# MainBoard.net
KiCad netlist of a schematic drawn in EAGLE
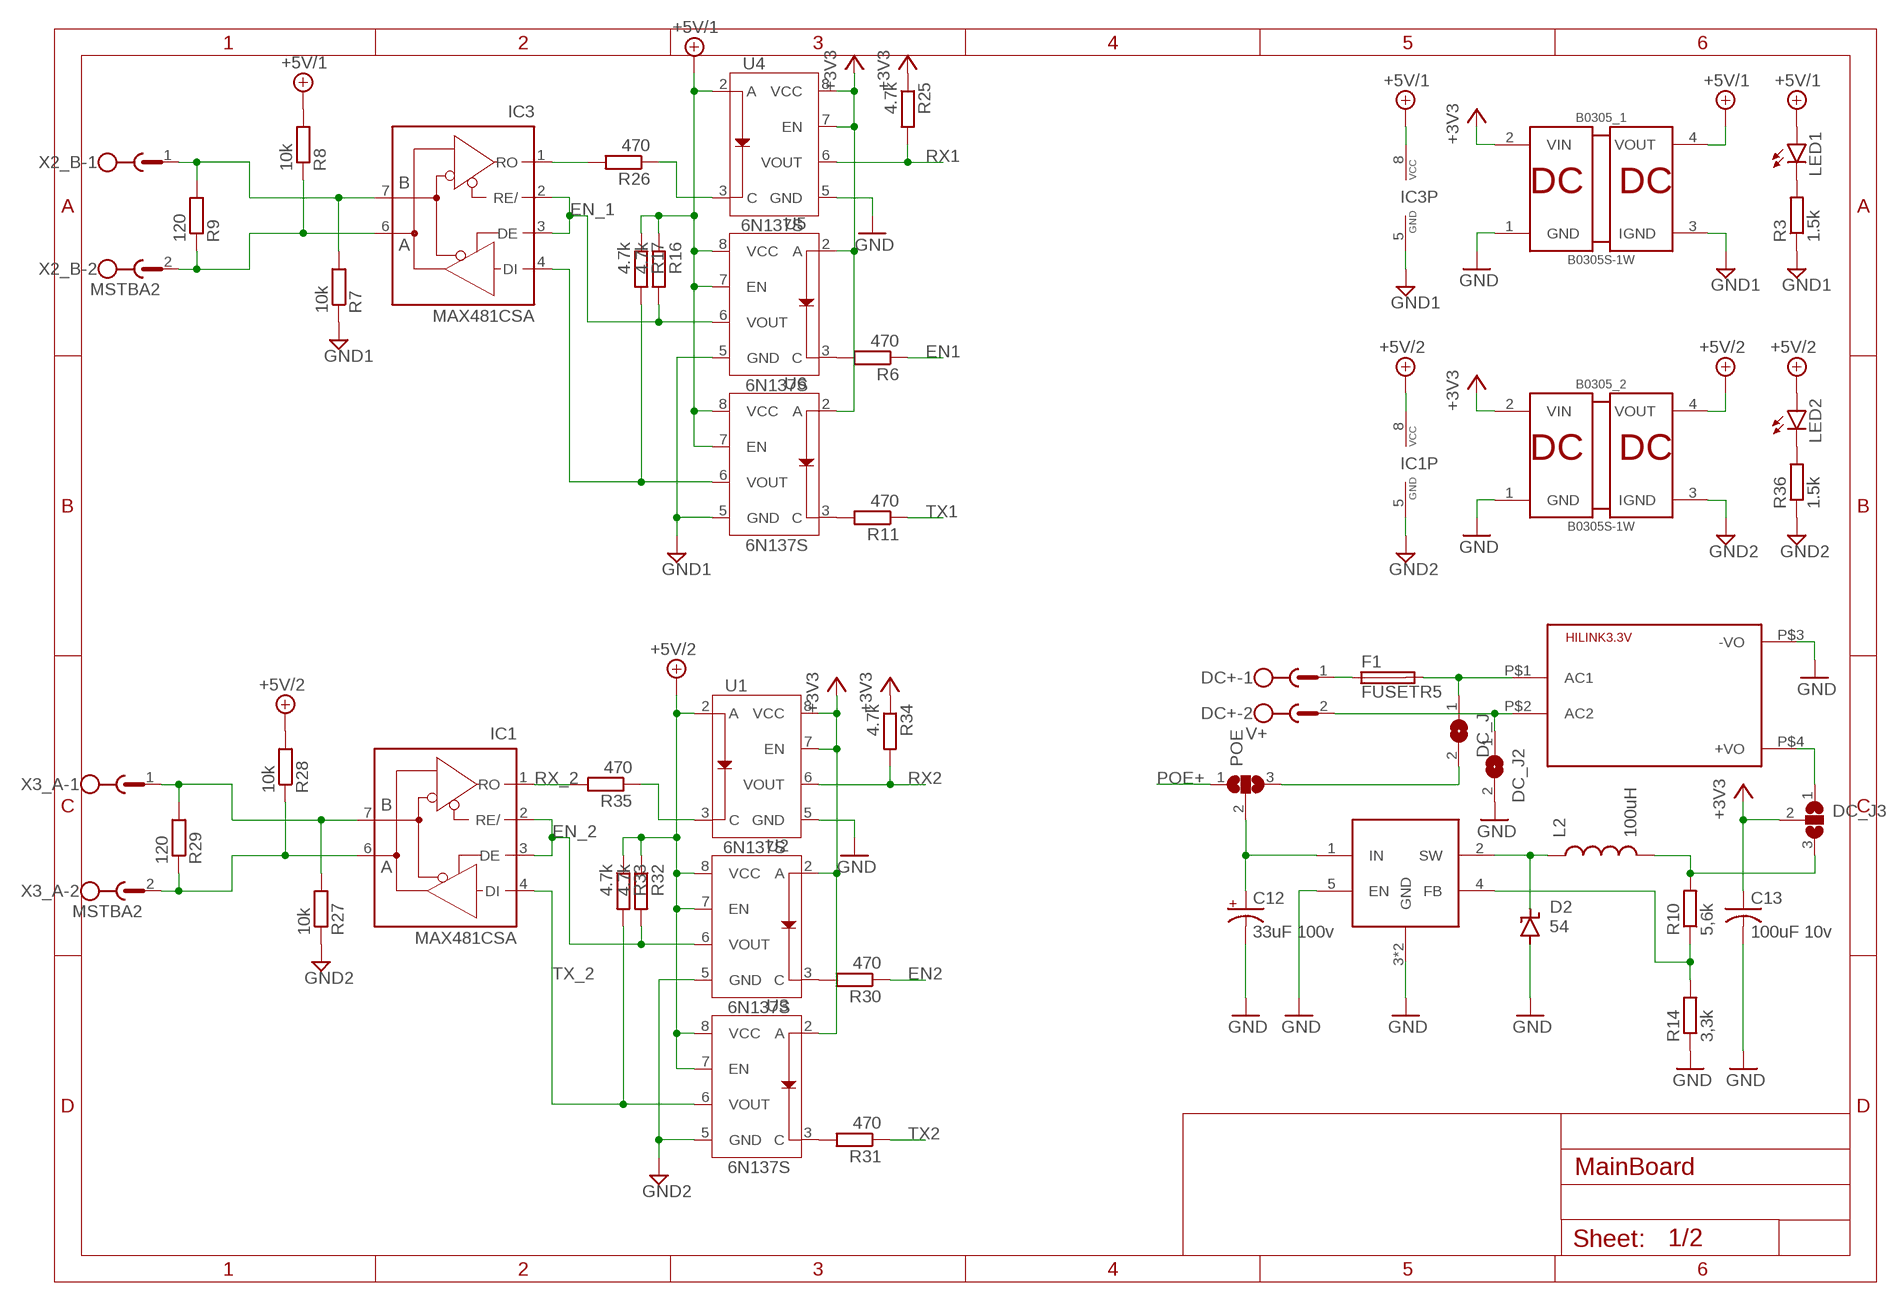
[diagram p0: schematic, sheet 1]
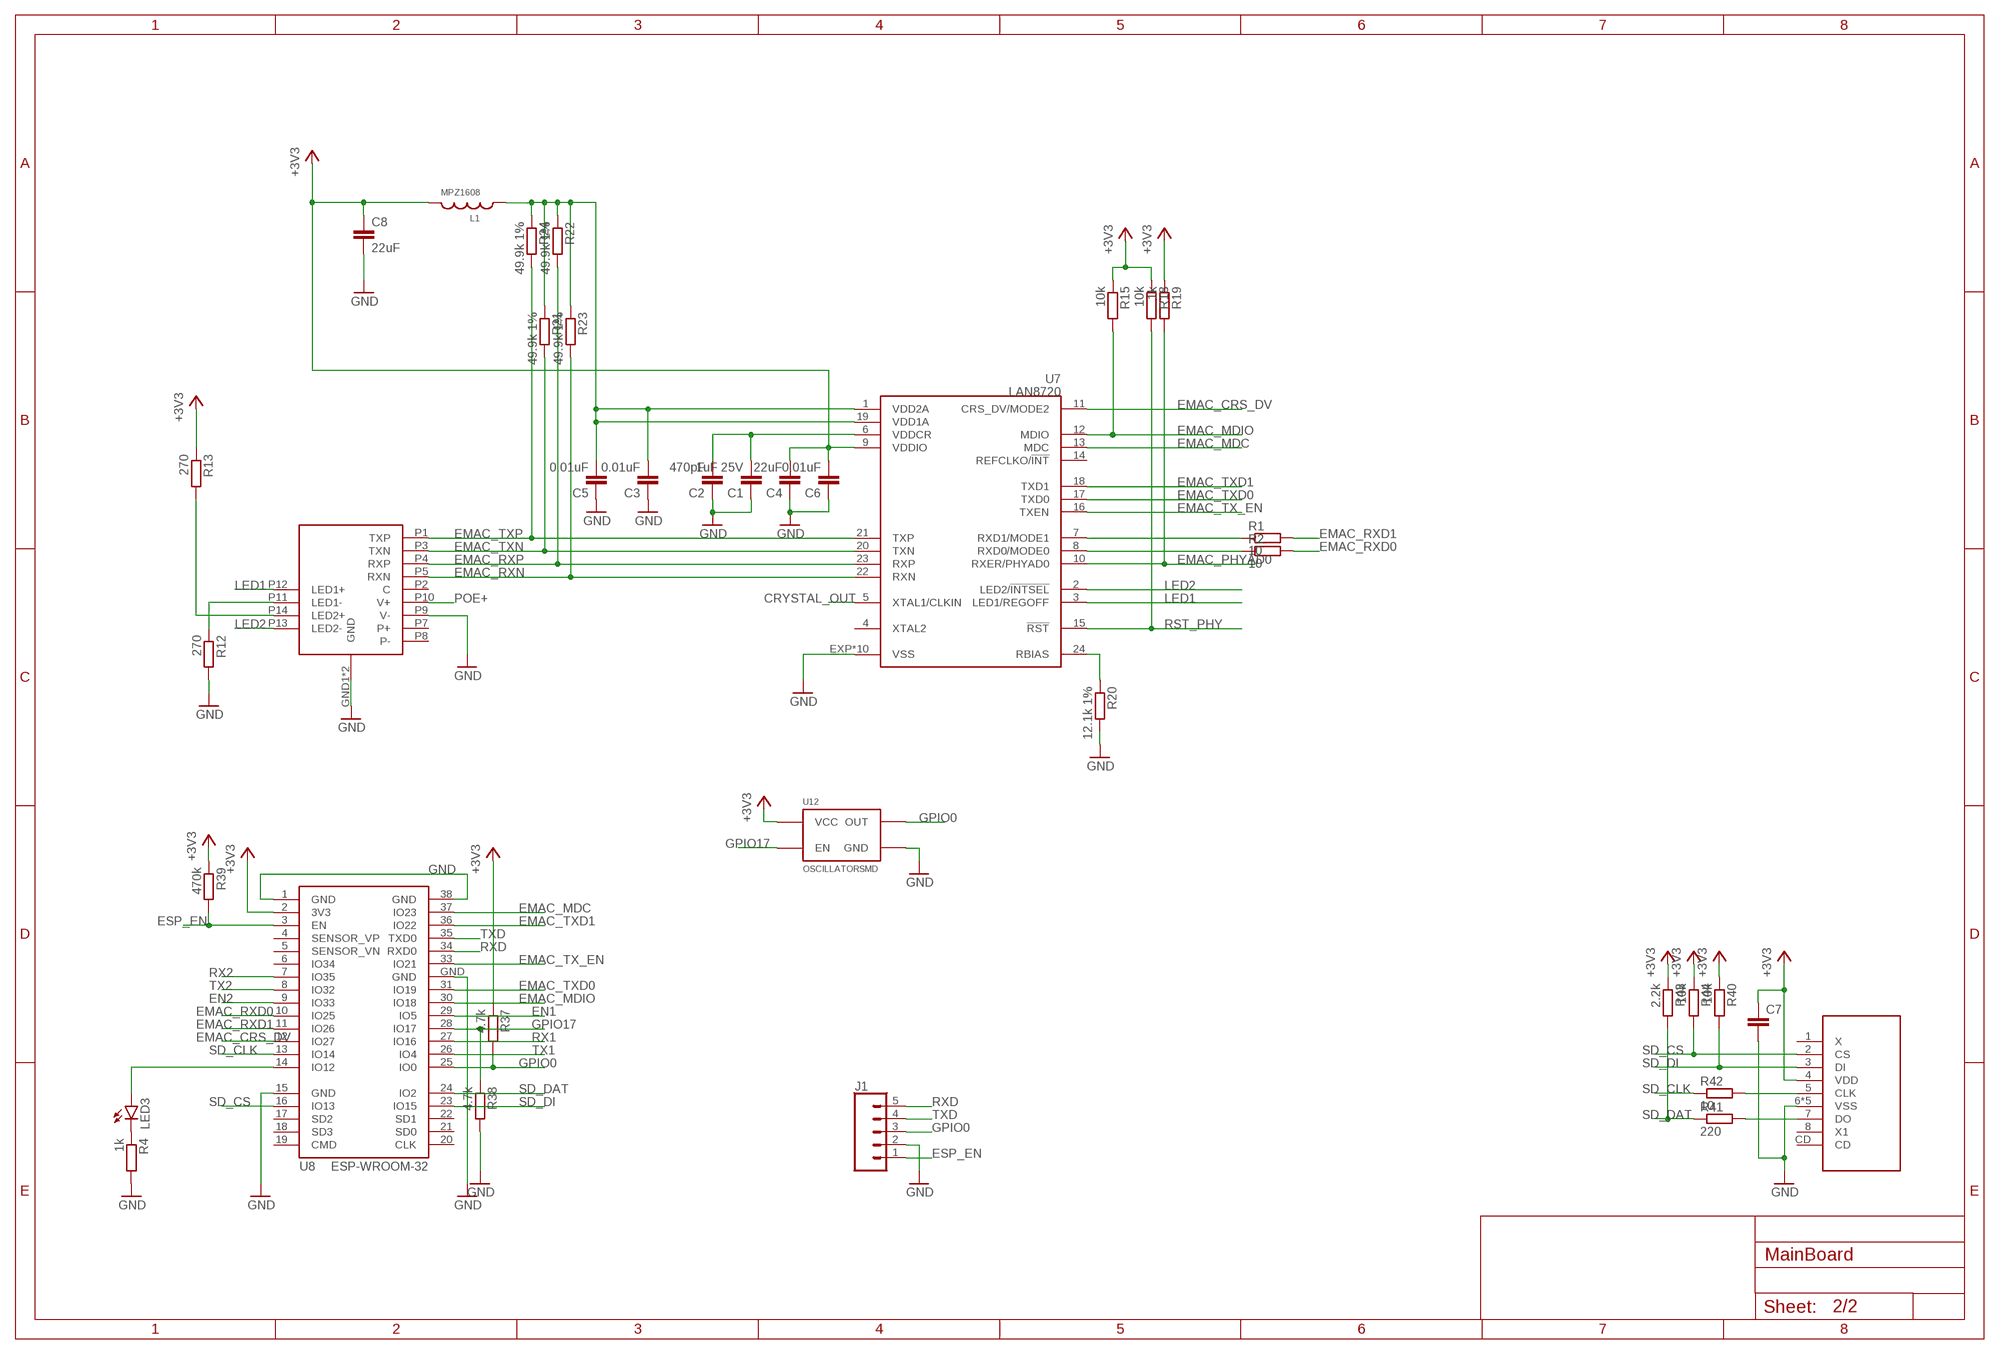
[diagram p1: schematic, sheet 2]

(export (version "E")
  (design (tool "Eeschema 10.0.6"))
  (components
    (comp (ref "C1")
      (value "1uF 25V")
      (footprint "eagle-import:C0805")
      (fields (field (name "MF") "YAGEO") (field (name "MPN") "CC0603KPX7R8BB105"))
      (libsource (lib "eagle-import") (part "C-EUC0805"))
    )
    (comp (ref "C2")
      (value "470pF")
      (footprint "eagle-import:C0805")
      (fields (field (name "MF") "YAGEO") (field (name "MPN") "CC0603JRX7R7BB471"))
      (libsource (lib "eagle-import") (part "C-EUC0805"))
    )
    (comp (ref "C3")
      (value "0.01uF")
      (footprint "eagle-import:C0805")
      (fields (field (name "MF") "YAGEO") (field (name "MPN") "CC0603KRX7R6BB103"))
      (libsource (lib "eagle-import") (part "C-EUC0805"))
    )
    (comp (ref "C4")
      (value "22uF")
      (footprint "eagle-import:C0805")
      (fields (field (name "MF") "YAGEO") (field (name "MPN") "CC0603KRX7R6BB103"))
      (libsource (lib "eagle-import") (part "C-EUC0805"))
    )
    (comp (ref "C5")
      (value "0.01uF")
      (footprint "eagle-import:C0805")
      (fields (field (name "MF") "YAGEO") (field (name "MPN") "CC0603KRX7R6BB103"))
      (libsource (lib "eagle-import") (part "C-EUC0805"))
    )
    (comp (ref "C6")
      (value "0.01uF")
      (footprint "eagle-import:C0805")
      (fields (field (name "MF") "YAGEO") (field (name "MPN") "CC0603KRX7R6BB103"))
      (libsource (lib "eagle-import") (part "C-EUC0805"))
    )
    (comp (ref "C7")
      (value "C-EUC1206")
      (footprint "eagle-import:C1206")
      (libsource (lib "eagle-import") (part "C-EUC1206"))
    )
    (comp (ref "C8")
      (value "22uF")
      (footprint "eagle-import:C0805")
      (fields (field (name "MF") "YAGEO") (field (name "MPN") "CC0603MPX5R5BB226"))
      (libsource (lib "eagle-import") (part "C-EUC0805"))
    )
    (comp (ref "J1")
      (value "CONN_05LOCK")
      (footprint "eagle-import:1X05_LOCK")
      (libsource (lib "eagle-import") (part "CONN_05LOCK"))
    )
    (comp (ref "L1")
      (value "MPZ1608")
      (footprint "eagle-import:1608")
      (libsource (lib "eagle-import") (part "MPZ1608"))
    )
    (comp (ref "LED3")
      (value "LEDSML1206")
      (footprint "eagle-import:SML1206")
      (libsource (lib "eagle-import") (part "LEDSML1206"))
    )
    (comp (ref "R1")
      (value "10")
      (footprint "eagle-import:R0805")
      (fields (field (name "MF") "YAGEO") (field (name "MPN") "RC0603JR-0727RL"))
      (libsource (lib "eagle-import") (part "R-EU_R0805"))
    )
    (comp (ref "R2")
      (value "10")
      (footprint "eagle-import:R0805")
      (fields (field (name "MF") "YAGEO") (field (name "MPN") "RC0603JR-0727RL"))
      (libsource (lib "eagle-import") (part "R-EU_R0805"))
    )
    (comp (ref "R4")
      (value "1k")
      (footprint "eagle-import:R0805")
      (fields (field (name "MF") "YAGEO") (field (name "MPN") "RC0603JR-07240RL"))
      (libsource (lib "eagle-import") (part "R-EU_R0805"))
    )
    (comp (ref "R12")
      (value "270")
      (footprint "eagle-import:R0805")
      (fields (field (name "MF") "YAGEO") (field (name "MPN") "RC0603JR-07240RL"))
      (libsource (lib "eagle-import") (part "R-EU_R0805"))
    )
    (comp (ref "R13")
      (value "270")
      (footprint "eagle-import:R0805")
      (fields (field (name "MF") "YAGEO") (field (name "MPN") "RC0603JR-07240RL"))
      (libsource (lib "eagle-import") (part "R-EU_R0805"))
    )
    (comp (ref "R15")
      (value "10k")
      (footprint "eagle-import:R0805")
      (fields (field (name "MF") "YAGEO") (field (name "MPN") "RC0603JR-0727RL"))
      (libsource (lib "eagle-import") (part "R-EU_R0805"))
    )
    (comp (ref "R18")
      (value "10k")
      (footprint "eagle-import:R0805")
      (fields (field (name "MF") "YAGEO") (field (name "MPN") "RC0603JR-0727RL"))
      (libsource (lib "eagle-import") (part "R-EU_R0805"))
    )
    (comp (ref "R19")
      (value "1k")
      (footprint "eagle-import:R0805")
      (fields (field (name "MF") "YAGEO") (field (name "MPN") "RC0603JR-0727RL"))
      (libsource (lib "eagle-import") (part "R-EU_R0805"))
    )
    (comp (ref "R20")
      (value "12.1k 1%")
      (footprint "eagle-import:R0805")
      (fields (field (name "MF") "YAGEO") (field (name "MPN") "RC0603JR-0727RL"))
      (libsource (lib "eagle-import") (part "R-EU_R0805"))
    )
    (comp (ref "R21")
      (value "49.9k 1%")
      (footprint "eagle-import:R0805")
      (fields (field (name "MF") "YAGEO") (field (name "MPN") "RC0603JR-0727RL"))
      (libsource (lib "eagle-import") (part "R-EU_R0805"))
    )
    (comp (ref "R22")
      (value "49.9k 1%")
      (footprint "eagle-import:R0805")
      (fields (field (name "MF") "YAGEO") (field (name "MPN") "RC0603JR-0727RL"))
      (libsource (lib "eagle-import") (part "R-EU_R0805"))
    )
    (comp (ref "R23")
      (value "49.9k 1%")
      (footprint "eagle-import:R0805")
      (fields (field (name "MF") "YAGEO") (field (name "MPN") "RC0603JR-0727RL"))
      (libsource (lib "eagle-import") (part "R-EU_R0805"))
    )
    (comp (ref "R24")
      (value "49.9k 1%")
      (footprint "eagle-import:R0805")
      (fields (field (name "MF") "YAGEO") (field (name "MPN") "RC0603JR-0727RL"))
      (libsource (lib "eagle-import") (part "R-EU_R0805"))
    )
    (comp (ref "R37")
      (value "4.7k")
      (footprint "eagle-import:R0805")
      (fields (field (name "MF") "YAGEO") (field (name "MPN") "RC0603JR-07240RL"))
      (libsource (lib "eagle-import") (part "R-EU_R0805"))
    )
    (comp (ref "R38")
      (value "4.7k")
      (footprint "eagle-import:R0805")
      (fields (field (name "MF") "YAGEO") (field (name "MPN") "RC0603JR-07240RL"))
      (libsource (lib "eagle-import") (part "R-EU_R0805"))
    )
    (comp (ref "R39")
      (value "470k")
      (footprint "eagle-import:R0805")
      (fields (field (name "MF") "YAGEO") (field (name "MPN") "RC0603JR-07240RL"))
      (libsource (lib "eagle-import") (part "R-EU_R0805"))
    )
    (comp (ref "R40")
      (value "10k")
      (footprint "eagle-import:R0805")
      (fields (field (name "MF") "YAGEO") (field (name "MPN") "RC0603JR-0727RL"))
      (libsource (lib "eagle-import") (part "R-EU_R0805"))
    )
    (comp (ref "R41")
      (value "220")
      (footprint "eagle-import:R0805")
      (fields (field (name "MF") "YAGEO") (field (name "MPN") "RC0603JR-0727RL"))
      (libsource (lib "eagle-import") (part "R-EU_R0805"))
    )
    (comp (ref "R42")
      (value "10")
      (footprint "eagle-import:R0805")
      (fields (field (name "MF") "YAGEO") (field (name "MPN") "RC0603JR-0727RL"))
      (libsource (lib "eagle-import") (part "R-EU_R0805"))
    )
    (comp (ref "R43")
      (value "2.2k")
      (footprint "eagle-import:R0805")
      (fields (field (name "MF") "YAGEO") (field (name "MPN") "RC0603JR-0727RL"))
      (libsource (lib "eagle-import") (part "R-EU_R0805"))
    )
    (comp (ref "R44")
      (value "10k")
      (footprint "eagle-import:R0805")
      (fields (field (name "MF") "YAGEO") (field (name "MPN") "RC0603JR-0727RL"))
      (libsource (lib "eagle-import") (part "R-EU_R0805"))
    )
    (comp (ref "U$1")
      (value "MICROSD")
      (footprint "eagle-import:MICROSDCARD")
      (libsource (lib "eagle-import") (part "MICROSD"))
    )
    (comp (ref "U$2")
      (value "RJ45-1169")
      (footprint "eagle-import:RJ45-1169")
      (libsource (lib "eagle-import") (part "RJ45-1169"))
    )
    (comp (ref "U7")
      (value "LAN8720")
      (footprint "eagle-import:QFN24")
      (fields (field (name "MF") "MICROCHIP TECHNOLOGY") (field (name "MPN") "LAN8720A-CP-ABC"))
      (libsource (lib "eagle-import") (part "LAN8720"))
    )
    (comp (ref "U8")
      (value "ESP-WROOM-32")
      (footprint "eagle-import:ESP-WROOM-32")
      (libsource (lib "eagle-import") (part "ESP-WROOM-32"))
    )
    (comp (ref "U12")
      (value "OSCILLATORSMD")
      (footprint "eagle-import:CRYSTAL-SMD-7X5")
      (libsource (lib "eagle-import") (part "OSCILLATORSMD"))
    )
    (comp (ref "B0305_1")
      (value "B0305S-1W")
      (footprint "eagle-import:B_S-1W")
      (libsource (lib "eagle-import") (part "B0305S-1W"))
    )
    (comp (ref "B0305_2")
      (value "B0305S-1W")
      (footprint "eagle-import:B_S-1W")
      (libsource (lib "eagle-import") (part "B0305S-1W"))
    )
    (comp (ref "C12")
      (value "33uF 100v")
      (footprint "eagle-import:150CLZ-0810")
      (libsource (lib "eagle-import") (part "CPOL-US150CLZ-0810"))
    )
    (comp (ref "C13")
      (value "100uF 10v")
      (footprint "eagle-import:C1206")
      (libsource (lib "eagle-import") (part "C-USC1206"))
    )
    (comp (ref "D2")
      (value "54")
      (footprint "eagle-import:SMBJ")
      (libsource (lib "eagle-import") (part "SUPPRESSOR-SMBJ"))
    )
    (comp (ref "DC+")
      (value "V+")
      (footprint "eagle-import:MSTBA2")
      (fields (field (name "MF") "FARNELL") (field (name "MPN") "1757242"))
      (libsource (lib "eagle-import") (part "MSTBA2"))
    )
    (comp (ref "DC_J")
      (value "SJW")
      (footprint "eagle-import:SJW")
      (libsource (lib "eagle-import") (part "SJW"))
    )
    (comp (ref "DC_J2")
      (value "SJW")
      (footprint "eagle-import:SJW")
      (libsource (lib "eagle-import") (part "SJW"))
    )
    (comp (ref "DC_J3")
      (value "SJ2W")
      (footprint "eagle-import:SJ_2")
      (libsource (lib "eagle-import") (part "SJ2W"))
    )
    (comp (ref "F1")
      (value "FUSETR5")
      (footprint "eagle-import:TR5")
      (libsource (lib "eagle-import") (part "FUSETR5"))
    )
    (comp (ref "HILINK3.3V")
      (value "HLK-PM013W")
      (footprint "eagle-import:HLK-PM01")
      (libsource (lib "eagle-import") (part "HLK-PM013W"))
    )
    (comp (ref "IC1")
      (value "MAX481CSA")
      (footprint "eagle-import:SO08")
      (fields (field (name "MF") "MAXIM"))
      (libsource (lib "eagle-import") (part "MAX481CSA"))
    )
    (comp (ref "IC3")
      (value "MAX481CSA")
      (footprint "eagle-import:SO08")
      (fields (field (name "MF") "MAXIM"))
      (libsource (lib "eagle-import") (part "MAX481CSA"))
    )
    (comp (ref "L2")
      (value "100uH")
      (footprint "eagle-import:CR75")
      (libsource (lib "eagle-import") (part "INDUCTOR68UH-1A"))
    )
    (comp (ref "LED1")
      (value "LEDSML1206")
      (footprint "eagle-import:SML1206")
      (libsource (lib "eagle-import") (part "LEDSML1206"))
    )
    (comp (ref "LED2")
      (value "LEDSML1206")
      (footprint "eagle-import:SML1206")
      (libsource (lib "eagle-import") (part "LEDSML1206"))
    )
    (comp (ref "POE")
      (value "SJ2W")
      (footprint "eagle-import:SJ_2")
      (libsource (lib "eagle-import") (part "SJ2W"))
    )
    (comp (ref "R3")
      (value "1.5k")
      (footprint "eagle-import:R0805")
      (libsource (lib "eagle-import") (part "R-EU_R0805"))
    )
    (comp (ref "R6")
      (value "470")
      (footprint "eagle-import:R0805")
      (libsource (lib "eagle-import") (part "R-EU_R0805"))
    )
    (comp (ref "R7")
      (value "10k")
      (footprint "eagle-import:R0805")
      (libsource (lib "eagle-import") (part "R-EU_R0805"))
    )
    (comp (ref "R8")
      (value "10k")
      (footprint "eagle-import:R0805")
      (libsource (lib "eagle-import") (part "R-EU_R0805"))
    )
    (comp (ref "R9")
      (value "120")
      (footprint "eagle-import:R0805")
      (libsource (lib "eagle-import") (part "R-EU_R0805"))
    )
    (comp (ref "R10")
      (value "5,6k")
      (footprint "eagle-import:R0805")
      (libsource (lib "eagle-import") (part "R-EU_R0805"))
    )
    (comp (ref "R11")
      (value "470")
      (footprint "eagle-import:R0805")
      (libsource (lib "eagle-import") (part "R-EU_R0805"))
    )
    (comp (ref "R14")
      (value "3,3k")
      (footprint "eagle-import:R0805")
      (libsource (lib "eagle-import") (part "R-EU_R0805"))
    )
    (comp (ref "R16")
      (value "4.7k")
      (footprint "eagle-import:R0805")
      (libsource (lib "eagle-import") (part "R-EU_R0805"))
    )
    (comp (ref "R17")
      (value "4.7k")
      (footprint "eagle-import:R0805")
      (libsource (lib "eagle-import") (part "R-EU_R0805"))
    )
    (comp (ref "R25")
      (value "4.7k")
      (footprint "eagle-import:R0805")
      (libsource (lib "eagle-import") (part "R-EU_R0805"))
    )
    (comp (ref "R26")
      (value "470")
      (footprint "eagle-import:R0805")
      (libsource (lib "eagle-import") (part "R-EU_R0805"))
    )
    (comp (ref "R27")
      (value "10k")
      (footprint "eagle-import:R0805")
      (libsource (lib "eagle-import") (part "R-EU_R0805"))
    )
    (comp (ref "R28")
      (value "10k")
      (footprint "eagle-import:R0805")
      (libsource (lib "eagle-import") (part "R-EU_R0805"))
    )
    (comp (ref "R29")
      (value "120")
      (footprint "eagle-import:R0805")
      (libsource (lib "eagle-import") (part "R-EU_R0805"))
    )
    (comp (ref "R30")
      (value "470")
      (footprint "eagle-import:R0805")
      (libsource (lib "eagle-import") (part "R-EU_R0805"))
    )
    (comp (ref "R31")
      (value "470")
      (footprint "eagle-import:R0805")
      (libsource (lib "eagle-import") (part "R-EU_R0805"))
    )
    (comp (ref "R32")
      (value "4.7k")
      (footprint "eagle-import:R0805")
      (libsource (lib "eagle-import") (part "R-EU_R0805"))
    )
    (comp (ref "R33")
      (value "4.7k")
      (footprint "eagle-import:R0805")
      (libsource (lib "eagle-import") (part "R-EU_R0805"))
    )
    (comp (ref "R34")
      (value "4.7k")
      (footprint "eagle-import:R0805")
      (libsource (lib "eagle-import") (part "R-EU_R0805"))
    )
    (comp (ref "R35")
      (value "470")
      (footprint "eagle-import:R0805")
      (libsource (lib "eagle-import") (part "R-EU_R0805"))
    )
    (comp (ref "R36")
      (value "1.5k")
      (footprint "eagle-import:R0805")
      (libsource (lib "eagle-import") (part "R-EU_R0805"))
    )
    (comp (ref "U1")
      (value "6N137S")
      (footprint "eagle-import:8-SMD")
      (libsource (lib "eagle-import") (part "6N137S"))
    )
    (comp (ref "U2")
      (value "6N137S")
      (footprint "eagle-import:8-SMD")
      (libsource (lib "eagle-import") (part "6N137S"))
    )
    (comp (ref "U3")
      (value "6N137S")
      (footprint "eagle-import:8-SMD")
      (libsource (lib "eagle-import") (part "6N137S"))
    )
    (comp (ref "U4")
      (value "6N137S")
      (footprint "eagle-import:8-SMD")
      (libsource (lib "eagle-import") (part "6N137S"))
    )
    (comp (ref "U5")
      (value "6N137S")
      (footprint "eagle-import:8-SMD")
      (libsource (lib "eagle-import") (part "6N137S"))
    )
    (comp (ref "U6")
      (value "6N137S")
      (footprint "eagle-import:8-SMD")
      (libsource (lib "eagle-import") (part "6N137S"))
    )
    (comp (ref "U9")
      (value "XL7015")
      (footprint "eagle-import:TO252-51")
      (libsource (lib "eagle-import") (part "XL7015"))
    )
    (comp (ref "X2_B")
      (value "MSTBA2")
      (footprint "eagle-import:MSTBA2")
      (fields (field (name "MF") "FARNELL") (field (name "MPN") "1757242"))
      (libsource (lib "eagle-import") (part "MSTBA2"))
    )
    (comp (ref "X3_A")
      (value "MSTBA2")
      (footprint "eagle-import:MSTBA2")
      (fields (field (name "MF") "FARNELL") (field (name "MPN") "1757242"))
      (libsource (lib "eagle-import") (part "MSTBA2"))
    )
  )
  (nets
    (net (code "1") (name "+3V3") (class "Default")
      (node (ref "B0305_1") (pin "2") (pinfunction "VIN_2") (pintype "passive"))
      (node (ref "B0305_2") (pin "2") (pinfunction "VIN_2") (pintype "passive"))
      (node (ref "C13") (pin "1") (pinfunction "1_1") (pintype "passive"))
      (node (ref "C4") (pin "2") (pinfunction "2_2") (pintype "passive"))
      (node (ref "C6") (pin "2") (pinfunction "2_2") (pintype "passive"))
      (node (ref "C7") (pin "1") (pinfunction "1_1") (pintype "passive"))
      (node (ref "C8") (pin "1") (pinfunction "1_1") (pintype "passive"))
      (node (ref "DC_J3") (pin "2") (pinfunction "2_2") (pintype "passive"))
      (node (ref "L1") (pin "P$2") (pinfunction "P$2_P$2") (pintype "bidirectional"))
      (node (ref "R13") (pin "1") (pinfunction "1_1") (pintype "passive"))
      (node (ref "R15") (pin "1") (pinfunction "1_1") (pintype "passive"))
      (node (ref "R18") (pin "1") (pinfunction "1_1") (pintype "passive"))
      (node (ref "R19") (pin "1") (pinfunction "1_1") (pintype "passive"))
      (node (ref "R25") (pin "1") (pinfunction "1_1") (pintype "passive"))
      (node (ref "R34") (pin "1") (pinfunction "1_1") (pintype "passive"))
      (node (ref "R37") (pin "1") (pinfunction "1_1") (pintype "passive"))
      (node (ref "R39") (pin "1") (pinfunction "1_1") (pintype "passive"))
      (node (ref "R40") (pin "1") (pinfunction "1_1") (pintype "passive"))
      (node (ref "R43") (pin "1") (pinfunction "1_1") (pintype "passive"))
      (node (ref "R44") (pin "1") (pinfunction "1_1") (pintype "passive"))
      (node (ref "U$1") (pin "4") (pinfunction "VDD_4") (pintype "bidirectional"))
      (node (ref "U1") (pin "7") (pinfunction "EN_7") (pintype "bidirectional"))
      (node (ref "U1") (pin "8") (pinfunction "VCC_8") (pintype "bidirectional"))
      (node (ref "U12") (pin "P$4") (pinfunction "VCC_P$4") (pintype "bidirectional"))
      (node (ref "U2") (pin "2") (pinfunction "A_2") (pintype "bidirectional"))
      (node (ref "U3") (pin "2") (pinfunction "A_2") (pintype "bidirectional"))
      (node (ref "U4") (pin "7") (pinfunction "EN_7") (pintype "bidirectional"))
      (node (ref "U4") (pin "8") (pinfunction "VCC_8") (pintype "bidirectional"))
      (node (ref "U5") (pin "2") (pinfunction "A_2") (pintype "bidirectional"))
      (node (ref "U6") (pin "2") (pinfunction "A_2") (pintype "bidirectional"))
      (node (ref "U7") (pin "9") (pinfunction "VDDIO_9") (pintype "power_in"))
      (node (ref "U8") (pin "2") (pinfunction "3V3_2") (pintype "power_in"))
    )
    (net (code "2") (name "+5V{slash}1") (class "Default")
      (node (ref "B0305_1") (pin "4") (pinfunction "VOUT_4") (pintype "passive"))
      (node (ref "IC3") (pin "8") (pinfunction "VCC_8") (pintype "power_in"))
      (node (ref "LED1") (pin "A") (pinfunction "A_A") (pintype "passive"))
      (node (ref "R16") (pin "1") (pinfunction "1_1") (pintype "passive"))
      (node (ref "R17") (pin "1") (pinfunction "1_1") (pintype "passive"))
      (node (ref "R8") (pin "2") (pinfunction "2_2") (pintype "passive"))
      (node (ref "U4") (pin "2") (pinfunction "A_2") (pintype "bidirectional"))
      (node (ref "U5") (pin "7") (pinfunction "EN_7") (pintype "bidirectional"))
      (node (ref "U5") (pin "8") (pinfunction "VCC_8") (pintype "bidirectional"))
      (node (ref "U6") (pin "7") (pinfunction "EN_7") (pintype "bidirectional"))
      (node (ref "U6") (pin "8") (pinfunction "VCC_8") (pintype "bidirectional"))
    )
    (net (code "3") (name "+5V{slash}2") (class "Default")
      (node (ref "B0305_2") (pin "4") (pinfunction "VOUT_4") (pintype "passive"))
      (node (ref "IC1") (pin "8") (pinfunction "VCC_8") (pintype "power_in"))
      (node (ref "LED2") (pin "A") (pinfunction "A_A") (pintype "passive"))
      (node (ref "R28") (pin "2") (pinfunction "2_2") (pintype "passive"))
      (node (ref "R32") (pin "1") (pinfunction "1_1") (pintype "passive"))
      (node (ref "R33") (pin "1") (pinfunction "1_1") (pintype "passive"))
      (node (ref "U1") (pin "2") (pinfunction "A_2") (pintype "bidirectional"))
      (node (ref "U2") (pin "7") (pinfunction "EN_7") (pintype "bidirectional"))
      (node (ref "U2") (pin "8") (pinfunction "VCC_8") (pintype "bidirectional"))
      (node (ref "U3") (pin "7") (pinfunction "EN_7") (pintype "bidirectional"))
      (node (ref "U3") (pin "8") (pinfunction "VCC_8") (pintype "bidirectional"))
    )
    (net (code "4") (name "CRYSTAL_OUT") (class "Default")
      (node (ref "U7") (pin "5") (pinfunction "XTAL1/CLKIN_5") (pintype "bidirectional"))
    )
    (net (code "5") (name "EMAC_CRS_DV") (class "Default")
      (node (ref "U7") (pin "11") (pinfunction "CRS_DV/MODE2_11") (pintype "bidirectional"))
      (node (ref "U8") (pin "12") (pinfunction "IO27_12") (pintype "bidirectional"))
    )
    (net (code "6") (name "EMAC_MDC") (class "Default")
      (node (ref "U7") (pin "13") (pinfunction "MDC_13") (pintype "bidirectional"))
      (node (ref "U8") (pin "37") (pinfunction "IO23_37") (pintype "bidirectional"))
    )
    (net (code "7") (name "EMAC_MDIO") (class "Default")
      (node (ref "R15") (pin "2") (pinfunction "2_2") (pintype "passive"))
      (node (ref "U7") (pin "12") (pinfunction "MDIO_12") (pintype "bidirectional"))
      (node (ref "U8") (pin "30") (pinfunction "IO18_30") (pintype "bidirectional"))
    )
    (net (code "8") (name "EMAC_PHYAD0") (class "Default")
      (node (ref "R19") (pin "2") (pinfunction "2_2") (pintype "passive"))
      (node (ref "U7") (pin "10") (pinfunction "RXER/PHYAD0_10") (pintype "bidirectional"))
    )
    (net (code "9") (name "EMAC_RXD0") (class "Default")
      (node (ref "R2") (pin "2") (pinfunction "2_2") (pintype "passive"))
      (node (ref "U8") (pin "10") (pinfunction "IO25_10") (pintype "bidirectional"))
    )
    (net (code "10") (name "EMAC_RXD1") (class "Default")
      (node (ref "R1") (pin "2") (pinfunction "2_2") (pintype "passive"))
      (node (ref "U8") (pin "11") (pinfunction "IO26_11") (pintype "bidirectional"))
    )
    (net (code "11") (name "EMAC_RXN") (class "Default")
      (node (ref "R23") (pin "2") (pinfunction "2_2") (pintype "passive"))
      (node (ref "U$2") (pin "P5") (pinfunction "RXN_P5") (pintype "bidirectional"))
      (node (ref "U7") (pin "22") (pinfunction "RXN_22") (pintype "bidirectional"))
    )
    (net (code "12") (name "EMAC_RXP") (class "Default")
      (node (ref "R22") (pin "2") (pinfunction "2_2") (pintype "passive"))
      (node (ref "U$2") (pin "P4") (pinfunction "RXP_P4") (pintype "bidirectional"))
      (node (ref "U7") (pin "23") (pinfunction "RXP_23") (pintype "bidirectional"))
    )
    (net (code "13") (name "EMAC_TXD0") (class "Default")
      (node (ref "U7") (pin "17") (pinfunction "TXD0_17") (pintype "bidirectional"))
      (node (ref "U8") (pin "31") (pinfunction "IO19_31") (pintype "bidirectional"))
    )
    (net (code "14") (name "EMAC_TXD1") (class "Default")
      (node (ref "U7") (pin "18") (pinfunction "TXD1_18") (pintype "bidirectional"))
      (node (ref "U8") (pin "36") (pinfunction "IO22_36") (pintype "bidirectional"))
    )
    (net (code "15") (name "EMAC_TXN") (class "Default")
      (node (ref "R21") (pin "2") (pinfunction "2_2") (pintype "passive"))
      (node (ref "U$2") (pin "P3") (pinfunction "TXN_P3") (pintype "bidirectional"))
      (node (ref "U7") (pin "20") (pinfunction "TXN_20") (pintype "bidirectional"))
    )
    (net (code "16") (name "EMAC_TXP") (class "Default")
      (node (ref "R24") (pin "2") (pinfunction "2_2") (pintype "passive"))
      (node (ref "U$2") (pin "P1") (pinfunction "TXP_P1") (pintype "bidirectional"))
      (node (ref "U7") (pin "21") (pinfunction "TXP_21") (pintype "bidirectional"))
    )
    (net (code "17") (name "EMAC_TX_EN") (class "Default")
      (node (ref "U7") (pin "16") (pinfunction "TXEN_16") (pintype "bidirectional"))
      (node (ref "U8") (pin "33") (pinfunction "IO21_33") (pintype "bidirectional"))
    )
    (net (code "18") (name "EN1") (class "Default")
      (node (ref "R6") (pin "1") (pinfunction "1_1") (pintype "passive"))
      (node (ref "U8") (pin "29") (pinfunction "IO5_29") (pintype "bidirectional"))
    )
    (net (code "19") (name "EN2") (class "Default")
      (node (ref "R30") (pin "1") (pinfunction "1_1") (pintype "passive"))
      (node (ref "U8") (pin "9") (pinfunction "IO33_9") (pintype "bidirectional"))
    )
    (net (code "20") (name "EN_1") (class "Default")
      (node (ref "IC3") (pin "2") (pinfunction "RE/_2") (pintype "input"))
      (node (ref "IC3") (pin "3") (pinfunction "DE_3") (pintype "input"))
      (node (ref "R16") (pin "2") (pinfunction "2_2") (pintype "passive"))
      (node (ref "U5") (pin "6") (pinfunction "VOUT_6") (pintype "bidirectional"))
    )
    (net (code "21") (name "EN_2") (class "Default")
      (node (ref "IC1") (pin "2") (pinfunction "RE/_2") (pintype "input"))
      (node (ref "IC1") (pin "3") (pinfunction "DE_3") (pintype "input"))
      (node (ref "R32") (pin "2") (pinfunction "2_2") (pintype "passive"))
      (node (ref "U2") (pin "6") (pinfunction "VOUT_6") (pintype "bidirectional"))
    )
    (net (code "22") (name "ESP_EN") (class "Default")
      (node (ref "J1") (pin "1") (pinfunction "1_1") (pintype "passive"))
      (node (ref "R39") (pin "2") (pinfunction "2_2") (pintype "passive"))
      (node (ref "U8") (pin "3") (pinfunction "EN_3") (pintype "input"))
    )
    (net (code "23") (name "GND") (class "Default")
      (node (ref "B0305_1") (pin "1") (pinfunction "GND_1") (pintype "passive"))
      (node (ref "B0305_2") (pin "1") (pinfunction "GND_1") (pintype "passive"))
      (node (ref "C1") (pin "1") (pinfunction "1_1") (pintype "passive"))
      (node (ref "C12") (pin "-") (pinfunction "-_-") (pintype "passive"))
      (node (ref "C13") (pin "2") (pinfunction "2_2") (pintype "passive"))
      (node (ref "C2") (pin "1") (pinfunction "1_1") (pintype "passive"))
      (node (ref "C3") (pin "1") (pinfunction "1_1") (pintype "passive"))
      (node (ref "C4") (pin "1") (pinfunction "1_1") (pintype "passive"))
      (node (ref "C5") (pin "1") (pinfunction "1_1") (pintype "passive"))
      (node (ref "C6") (pin "1") (pinfunction "1_1") (pintype "passive"))
      (node (ref "C7") (pin "2") (pinfunction "2_2") (pintype "passive"))
      (node (ref "C8") (pin "2") (pinfunction "2_2") (pintype "passive"))
      (node (ref "D2") (pin "A") (pinfunction "A_A") (pintype "passive"))
      (node (ref "DC_J2") (pin "2") (pinfunction "2_2") (pintype "passive"))
      (node (ref "HILINK3.3V") (pin "P$3") (pinfunction "-VO_P$3") (pintype "bidirectional"))
      (node (ref "J1") (pin "2") (pinfunction "2_2") (pintype "passive"))
      (node (ref "R12") (pin "2") (pinfunction "2_2") (pintype "passive"))
      (node (ref "R14") (pin "1") (pinfunction "1_1") (pintype "passive"))
      (node (ref "R20") (pin "2") (pinfunction "2_2") (pintype "passive"))
      (node (ref "R38") (pin "2") (pinfunction "2_2") (pintype "passive"))
      (node (ref "R4") (pin "2") (pinfunction "2_2") (pintype "passive"))
      (node (ref "U$1") (pin "6") (pinfunction "VSS_6") (pintype "bidirectional"))
      (node (ref "U$1") (pin "GND") (pinfunction "VSS_GND") (pintype "bidirectional"))
      (node (ref "U$1") (pin "GND1") (pinfunction "VSS_GND1") (pintype "bidirectional"))
      (node (ref "U$1") (pin "GND2") (pinfunction "VSS_GND2") (pintype "bidirectional"))
      (node (ref "U$1") (pin "GND3") (pinfunction "VSS_GND3") (pintype "bidirectional"))
      (node (ref "U$2") (pin "GND1") (pinfunction "GND_GND1") (pintype "bidirectional"))
      (node (ref "U$2") (pin "GND2") (pinfunction "GND_GND2") (pintype "bidirectional"))
      (node (ref "U$2") (pin "P9") (pinfunction "V-_P9") (pintype "bidirectional"))
      (node (ref "U1") (pin "5") (pinfunction "GND_5") (pintype "bidirectional"))
      (node (ref "U12") (pin "P$2") (pinfunction "GND_P$2") (pintype "bidirectional"))
      (node (ref "U4") (pin "5") (pinfunction "GND_5") (pintype "bidirectional"))
      (node (ref "U7") (pin "EXP") (pinfunction "VSS_EXP") (pintype "power_in"))
      (node (ref "U7") (pin "GND1") (pinfunction "VSS_GND1") (pintype "power_in"))
      (node (ref "U7") (pin "GND2") (pinfunction "VSS_GND2") (pintype "power_in"))
      (node (ref "U7") (pin "GND3") (pinfunction "VSS_GND3") (pintype "power_in"))
      (node (ref "U7") (pin "GND4") (pinfunction "VSS_GND4") (pintype "power_in"))
      (node (ref "U7") (pin "GND5") (pinfunction "VSS_GND5") (pintype "power_in"))
      (node (ref "U7") (pin "GND6") (pinfunction "VSS_GND6") (pintype "power_in"))
      (node (ref "U7") (pin "GND7") (pinfunction "VSS_GND7") (pintype "power_in"))
      (node (ref "U7") (pin "GND8") (pinfunction "VSS_GND8") (pintype "power_in"))
      (node (ref "U7") (pin "GND9") (pinfunction "VSS_GND9") (pintype "power_in"))
      (node (ref "U8") (pin "1") (pinfunction "GND_1") (pintype "power_in"))
      (node (ref "U8") (pin "15") (pinfunction "GND_15") (pintype "power_in"))
      (node (ref "U8") (pin "38") (pinfunction "GND_38") (pintype "power_in"))
      (node (ref "U8") (pin "GND") (pinfunction "GND_GND") (pintype "power_in"))
      (node (ref "U9") (pin "3") (pinfunction "GND_3") (pintype "bidirectional"))
      (node (ref "U9") (pin "5") (pinfunction "EN_5") (pintype "bidirectional"))
      (node (ref "U9") (pin "GND") (pinfunction "GND_GND") (pintype "bidirectional"))
    )
    (net (code "24") (name "GND1") (class "Default")
      (node (ref "B0305_1") (pin "3") (pinfunction "IGND_3") (pintype "passive"))
      (node (ref "IC3") (pin "5") (pinfunction "GND_5") (pintype "power_in"))
      (node (ref "R3") (pin "1") (pinfunction "1_1") (pintype "passive"))
      (node (ref "R7") (pin "1") (pinfunction "1_1") (pintype "passive"))
      (node (ref "U5") (pin "5") (pinfunction "GND_5") (pintype "bidirectional"))
      (node (ref "U6") (pin "5") (pinfunction "GND_5") (pintype "bidirectional"))
    )
    (net (code "25") (name "GND2") (class "Default")
      (node (ref "B0305_2") (pin "3") (pinfunction "IGND_3") (pintype "passive"))
      (node (ref "IC1") (pin "5") (pinfunction "GND_5") (pintype "power_in"))
      (node (ref "R27") (pin "1") (pinfunction "1_1") (pintype "passive"))
      (node (ref "R36") (pin "1") (pinfunction "1_1") (pintype "passive"))
      (node (ref "U2") (pin "5") (pinfunction "GND_5") (pintype "bidirectional"))
      (node (ref "U3") (pin "5") (pinfunction "GND_5") (pintype "bidirectional"))
    )
    (net (code "26") (name "GPIO0") (class "Default")
      (node (ref "J1") (pin "3") (pinfunction "3_3") (pintype "passive"))
      (node (ref "R37") (pin "2") (pinfunction "2_2") (pintype "passive"))
      (node (ref "U12") (pin "P$3") (pinfunction "OUT_P$3") (pintype "bidirectional"))
      (node (ref "U8") (pin "25") (pinfunction "IO0_25") (pintype "bidirectional"))
    )
    (net (code "27") (name "GPIO17") (class "Default")
      (node (ref "R38") (pin "1") (pinfunction "1_1") (pintype "passive"))
      (node (ref "U12") (pin "P$1") (pinfunction "EN_P$1") (pintype "bidirectional"))
      (node (ref "U8") (pin "28") (pinfunction "IO17_28") (pintype "bidirectional"))
    )
    (net (code "28") (name "LED1") (class "Default")
      (node (ref "U$2") (pin "P12") (pinfunction "LED1+_P12") (pintype "bidirectional"))
      (node (ref "U7") (pin "3") (pinfunction "LED1/REGOFF_3") (pintype "bidirectional"))
    )
    (net (code "29") (name "LED2") (class "Default")
      (node (ref "U$2") (pin "P13") (pinfunction "LED2-_P13") (pintype "bidirectional"))
      (node (ref "U7") (pin "2") (pinfunction "LED2/~{INTSEL}_2") (pintype "bidirectional"))
    )
    (net (code "30") (name "Net-(DC+-Pad1)") (class "Default")
      (node (ref "DC+") (pin "1") (pinfunction "1_1") (pintype "passive"))
      (node (ref "F1") (pin "1") (pinfunction "1_1") (pintype "passive"))
    )
    (net (code "31") (name "Net-(DC+B-1)") (class "Default")
      (node (ref "DC+") (pin "2") (pinfunction "1_2") (pintype "passive"))
      (node (ref "DC_J2") (pin "1") (pinfunction "1_1") (pintype "passive"))
      (node (ref "HILINK3.3V") (pin "P$2") (pinfunction "AC2_P$2") (pintype "bidirectional"))
    )
    (net (code "32") (name "Net-(DC_J-Pad2)") (class "Default")
      (node (ref "DC_J") (pin "2") (pinfunction "2_2") (pintype "passive"))
      (node (ref "POE") (pin "3") (pinfunction "3_3") (pintype "passive"))
    )
    (net (code "33") (name "Net-(HILINK3.3V-+VO)") (class "Default")
      (node (ref "DC_J3") (pin "1") (pinfunction "1_1") (pintype "passive"))
      (node (ref "HILINK3.3V") (pin "P$4") (pinfunction "+VO_P$4") (pintype "bidirectional"))
    )
    (net (code "34") (name "Net-(HILINK3.3V-AC1)") (class "Default")
      (node (ref "DC_J") (pin "1") (pinfunction "1_1") (pintype "passive"))
      (node (ref "F1") (pin "2") (pinfunction "2_2") (pintype "passive"))
      (node (ref "HILINK3.3V") (pin "P$1") (pinfunction "AC1_P$1") (pintype "bidirectional"))
    )
    (net (code "35") (name "Net-(IC1A-A)") (class "Default")
      (node (ref "IC1") (pin "6") (pinfunction "A_6") (pintype "passive"))
      (node (ref "R28") (pin "1") (pinfunction "1_1") (pintype "passive"))
      (node (ref "R29") (pin "1") (pinfunction "1_1") (pintype "passive"))
      (node (ref "X3_A") (pin "2") (pinfunction "1_2") (pintype "passive"))
    )
    (net (code "36") (name "Net-(IC1A-B)") (class "Default")
      (node (ref "IC1") (pin "7") (pinfunction "B_7") (pintype "passive"))
      (node (ref "R27") (pin "2") (pinfunction "2_2") (pintype "passive"))
      (node (ref "R29") (pin "2") (pinfunction "2_2") (pintype "passive"))
      (node (ref "X3_A") (pin "1") (pinfunction "1_1") (pintype "passive"))
    )
    (net (code "37") (name "Net-(IC3A-A)") (class "Default")
      (node (ref "IC3") (pin "6") (pinfunction "A_6") (pintype "passive"))
      (node (ref "R8") (pin "1") (pinfunction "1_1") (pintype "passive"))
      (node (ref "R9") (pin "1") (pinfunction "1_1") (pintype "passive"))
      (node (ref "X2_B") (pin "2") (pinfunction "1_2") (pintype "passive"))
    )
    (net (code "38") (name "Net-(IC3A-B)") (class "Default")
      (node (ref "IC3") (pin "7") (pinfunction "B_7") (pintype "passive"))
      (node (ref "R7") (pin "2") (pinfunction "2_2") (pintype "passive"))
      (node (ref "R9") (pin "2") (pinfunction "2_2") (pintype "passive"))
      (node (ref "X2_B") (pin "1") (pinfunction "1_1") (pintype "passive"))
    )
    (net (code "39") (name "Net-(IC3A-DI)") (class "Default")
      (node (ref "IC3") (pin "4") (pinfunction "DI_4") (pintype "input"))
      (node (ref "R17") (pin "2") (pinfunction "2_2") (pintype "passive"))
      (node (ref "U6") (pin "6") (pinfunction "VOUT_6") (pintype "bidirectional"))
    )
    (net (code "40") (name "Net-(IC3A-RO)") (class "Default")
      (node (ref "IC3") (pin "1") (pinfunction "RO_1") (pintype "output"))
      (node (ref "R26") (pin "2") (pinfunction "2_2") (pintype "passive"))
    )
    (net (code "41") (name "Net-(L2-1)") (class "Default")
      (node (ref "D2") (pin "C") (pinfunction "C_C") (pintype "passive"))
      (node (ref "L2") (pin "P$1") (pinfunction "1_P$1") (pintype "passive"))
      (node (ref "U9") (pin "2") (pinfunction "SW_2") (pintype "bidirectional"))
    )
    (net (code "42") (name "Net-(L2-2)") (class "Default")
      (node (ref "DC_J3") (pin "3") (pinfunction "3_3") (pintype "passive"))
      (node (ref "L2") (pin "P$2") (pinfunction "2_P$2") (pintype "passive"))
      (node (ref "R10") (pin "2") (pinfunction "2_2") (pintype "passive"))
    )
    (net (code "43") (name "Net-(LED1-PadC)") (class "Default")
      (node (ref "LED1") (pin "C") (pinfunction "C_C") (pintype "passive"))
      (node (ref "R3") (pin "2") (pinfunction "2_2") (pintype "passive"))
    )
    (net (code "44") (name "Net-(LED2-PadC)") (class "Default")
      (node (ref "LED2") (pin "C") (pinfunction "C_C") (pintype "passive"))
      (node (ref "R36") (pin "2") (pinfunction "2_2") (pintype "passive"))
    )
    (net (code "45") (name "Net-(LED3-PadC)") (class "Default")
      (node (ref "LED3") (pin "C") (pinfunction "C_C") (pintype "passive"))
      (node (ref "R4") (pin "1") (pinfunction "1_1") (pintype "passive"))
    )
    (net (code "46") (name "Net-(U$1-CLK)") (class "Default")
      (node (ref "R42") (pin "2") (pinfunction "2_2") (pintype "passive"))
      (node (ref "U$1") (pin "5") (pinfunction "CLK_5") (pintype "bidirectional"))
    )
    (net (code "47") (name "Net-(U$1-DO)") (class "Default")
      (node (ref "R41") (pin "2") (pinfunction "2_2") (pintype "passive"))
      (node (ref "U$1") (pin "7") (pinfunction "DO_7") (pintype "bidirectional"))
    )
    (net (code "48") (name "Net-(U$2-LED1-)") (class "Default")
      (node (ref "R12") (pin "1") (pinfunction "1_1") (pintype "passive"))
      (node (ref "U$2") (pin "P11") (pinfunction "LED1-_P11") (pintype "bidirectional"))
    )
    (net (code "49") (name "Net-(U$2-LED2+)") (class "Default")
      (node (ref "R13") (pin "2") (pinfunction "2_2") (pintype "passive"))
      (node (ref "U$2") (pin "P14") (pinfunction "LED2+_P14") (pintype "bidirectional"))
    )
    (net (code "50") (name "Net-(U1-C)") (class "Default")
      (node (ref "R35") (pin "1") (pinfunction "1_1") (pintype "passive"))
      (node (ref "U1") (pin "3") (pinfunction "C_3") (pintype "bidirectional"))
    )
    (net (code "51") (name "Net-(U2-C)") (class "Default")
      (node (ref "R30") (pin "2") (pinfunction "2_2") (pintype "passive"))
      (node (ref "U2") (pin "3") (pinfunction "C_3") (pintype "bidirectional"))
    )
    (net (code "52") (name "Net-(U3-C)") (class "Default")
      (node (ref "R31") (pin "2") (pinfunction "2_2") (pintype "passive"))
      (node (ref "U3") (pin "3") (pinfunction "C_3") (pintype "bidirectional"))
    )
    (net (code "53") (name "Net-(U4-C)") (class "Default")
      (node (ref "R26") (pin "1") (pinfunction "1_1") (pintype "passive"))
      (node (ref "U4") (pin "3") (pinfunction "C_3") (pintype "bidirectional"))
    )
    (net (code "54") (name "Net-(U5-C)") (class "Default")
      (node (ref "R6") (pin "2") (pinfunction "2_2") (pintype "passive"))
      (node (ref "U5") (pin "3") (pinfunction "C_3") (pintype "bidirectional"))
    )
    (net (code "55") (name "Net-(U6-C)") (class "Default")
      (node (ref "R11") (pin "2") (pinfunction "2_2") (pintype "passive"))
      (node (ref "U6") (pin "3") (pinfunction "C_3") (pintype "bidirectional"))
    )
    (net (code "56") (name "Net-(U7-RBIAS)") (class "Default")
      (node (ref "R20") (pin "1") (pinfunction "1_1") (pintype "passive"))
      (node (ref "U7") (pin "24") (pinfunction "RBIAS_24") (pintype "bidirectional"))
    )
    (net (code "57") (name "Net-(U7-RXD0{slash}MODE0)") (class "Default")
      (node (ref "R2") (pin "1") (pinfunction "1_1") (pintype "passive"))
      (node (ref "U7") (pin "8") (pinfunction "RXD0/MODE0_8") (pintype "bidirectional"))
    )
    (net (code "58") (name "Net-(U7-RXD1{slash}MODE1)") (class "Default")
      (node (ref "R1") (pin "1") (pinfunction "1_1") (pintype "passive"))
      (node (ref "U7") (pin "7") (pinfunction "RXD1/MODE1_7") (pintype "bidirectional"))
    )
    (net (code "59") (name "Net-(U7-VDD1A)") (class "Default")
      (node (ref "C3") (pin "2") (pinfunction "2_2") (pintype "passive"))
      (node (ref "C5") (pin "2") (pinfunction "2_2") (pintype "passive"))
      (node (ref "L1") (pin "P$1") (pinfunction "P$1_P$1") (pintype "bidirectional"))
      (node (ref "R21") (pin "1") (pinfunction "1_1") (pintype "passive"))
      (node (ref "R22") (pin "1") (pinfunction "1_1") (pintype "passive"))
      (node (ref "R23") (pin "1") (pinfunction "1_1") (pintype "passive"))
      (node (ref "R24") (pin "1") (pinfunction "1_1") (pintype "passive"))
      (node (ref "U7") (pin "1") (pinfunction "VDD2A_1") (pintype "power_in"))
      (node (ref "U7") (pin "19") (pinfunction "VDD1A_19") (pintype "power_in"))
    )
    (net (code "60") (name "Net-(U7-VDDCR)") (class "Default")
      (node (ref "C1") (pin "2") (pinfunction "2_2") (pintype "passive"))
      (node (ref "C2") (pin "2") (pinfunction "2_2") (pintype "passive"))
      (node (ref "U7") (pin "6") (pinfunction "VDDCR_6") (pintype "power_in"))
    )
    (net (code "61") (name "Net-(U8-IO12)") (class "Default")
      (node (ref "LED3") (pin "A") (pinfunction "A_A") (pintype "passive"))
      (node (ref "U8") (pin "14") (pinfunction "IO12_14") (pintype "bidirectional"))
    )
    (net (code "62") (name "Net-(U9-FB)") (class "Default")
      (node (ref "R10") (pin "1") (pinfunction "1_1") (pintype "passive"))
      (node (ref "R14") (pin "2") (pinfunction "2_2") (pintype "passive"))
      (node (ref "U9") (pin "4") (pinfunction "FB_4") (pintype "bidirectional"))
    )
    (net (code "63") (name "Net-(U9-IN)") (class "Default")
      (node (ref "C12") (pin "+") (pinfunction "+_+") (pintype "passive"))
      (node (ref "POE") (pin "2") (pinfunction "2_2") (pintype "passive"))
      (node (ref "U9") (pin "1") (pinfunction "IN_1") (pintype "bidirectional"))
    )
    (net (code "64") (name "POE+") (class "Default")
      (node (ref "POE") (pin "1") (pinfunction "1_1") (pintype "passive"))
      (node (ref "U$2") (pin "P10") (pinfunction "V+_P10") (pintype "bidirectional"))
    )
    (net (code "65") (name "RST_PHY") (class "Default")
      (node (ref "R18") (pin "2") (pinfunction "2_2") (pintype "passive"))
      (node (ref "U7") (pin "15") (pinfunction "~{RST}_15") (pintype "bidirectional"))
    )
    (net (code "66") (name "RX1") (class "Default")
      (node (ref "R25") (pin "2") (pinfunction "2_2") (pintype "passive"))
      (node (ref "U4") (pin "6") (pinfunction "VOUT_6") (pintype "bidirectional"))
      (node (ref "U8") (pin "27") (pinfunction "IO16_27") (pintype "bidirectional"))
    )
    (net (code "67") (name "RX2") (class "Default")
      (node (ref "R34") (pin "2") (pinfunction "2_2") (pintype "passive"))
      (node (ref "U1") (pin "6") (pinfunction "VOUT_6") (pintype "bidirectional"))
      (node (ref "U8") (pin "7") (pinfunction "IO35_7") (pintype "bidirectional"))
    )
    (net (code "68") (name "RXD") (class "Default")
      (node (ref "J1") (pin "5") (pinfunction "5_5") (pintype "passive"))
      (node (ref "U8") (pin "34") (pinfunction "RXD0_34") (pintype "bidirectional"))
    )
    (net (code "69") (name "RX_2") (class "Default")
      (node (ref "IC1") (pin "1") (pinfunction "RO_1") (pintype "output"))
      (node (ref "R35") (pin "2") (pinfunction "2_2") (pintype "passive"))
    )
    (net (code "70") (name "SD_CLK") (class "Default")
      (node (ref "R42") (pin "1") (pinfunction "1_1") (pintype "passive"))
      (node (ref "U8") (pin "13") (pinfunction "IO14_13") (pintype "bidirectional"))
    )
    (net (code "71") (name "SD_CS") (class "Default")
      (node (ref "R44") (pin "2") (pinfunction "2_2") (pintype "passive"))
      (node (ref "U$1") (pin "2") (pinfunction "CS_2") (pintype "bidirectional"))
      (node (ref "U8") (pin "16") (pinfunction "IO13_16") (pintype "bidirectional"))
    )
    (net (code "72") (name "SD_DAT") (class "Default")
      (node (ref "R41") (pin "1") (pinfunction "1_1") (pintype "passive"))
      (node (ref "R43") (pin "2") (pinfunction "2_2") (pintype "passive"))
      (node (ref "U8") (pin "24") (pinfunction "IO2_24") (pintype "bidirectional"))
    )
    (net (code "73") (name "SD_DI") (class "Default")
      (node (ref "R40") (pin "2") (pinfunction "2_2") (pintype "passive"))
      (node (ref "U$1") (pin "3") (pinfunction "DI_3") (pintype "bidirectional"))
      (node (ref "U8") (pin "23") (pinfunction "IO15_23") (pintype "bidirectional"))
    )
    (net (code "74") (name "TX1") (class "Default")
      (node (ref "R11") (pin "1") (pinfunction "1_1") (pintype "passive"))
      (node (ref "U8") (pin "26") (pinfunction "IO4_26") (pintype "bidirectional"))
    )
    (net (code "75") (name "TX2") (class "Default")
      (node (ref "R31") (pin "1") (pinfunction "1_1") (pintype "passive"))
      (node (ref "U8") (pin "8") (pinfunction "IO32_8") (pintype "bidirectional"))
    )
    (net (code "76") (name "TXD") (class "Default")
      (node (ref "J1") (pin "4") (pinfunction "4_4") (pintype "passive"))
      (node (ref "U8") (pin "35") (pinfunction "TXD0_35") (pintype "bidirectional"))
    )
    (net (code "77") (name "TX_2") (class "Default")
      (node (ref "IC1") (pin "4") (pinfunction "DI_4") (pintype "input"))
      (node (ref "R33") (pin "2") (pinfunction "2_2") (pintype "passive"))
      (node (ref "U3") (pin "6") (pinfunction "VOUT_6") (pintype "bidirectional"))
    )
    (net (code "78") (name "unconnected-(U$1-PadCD)") (class "Default")
      (node (ref "U$1") (pin "CD") (pinfunction "CD_CD") (pintype "bidirectional"))
    )
    (net (code "79") (name "unconnected-(U$1-X-Pad1)") (class "Default")
      (node (ref "U$1") (pin "1") (pinfunction "X_1") (pintype "bidirectional"))
    )
    (net (code "80") (name "unconnected-(U$1-X1-Pad8)") (class "Default")
      (node (ref "U$1") (pin "8") (pinfunction "X1_8") (pintype "bidirectional"))
    )
    (net (code "81") (name "unconnected-(U$2-C-PadP2)") (class "Default")
      (node (ref "U$2") (pin "P2") (pinfunction "C_P2") (pintype "bidirectional"))
    )
    (net (code "82") (name "unconnected-(U$2-P+-PadP7)") (class "Default")
      (node (ref "U$2") (pin "P7") (pinfunction "P+_P7") (pintype "bidirectional"))
    )
    (net (code "83") (name "unconnected-(U$2-P--PadP8)") (class "Default")
      (node (ref "U$2") (pin "P8") (pinfunction "P-_P8") (pintype "bidirectional"))
    )
    (net (code "84") (name "unconnected-(U7-REFCLKO{slash}~{INT}-Pad14)") (class "Default")
      (node (ref "U7") (pin "14") (pinfunction "REFCLKO/~{INT}_14") (pintype "bidirectional"))
    )
    (net (code "85") (name "unconnected-(U7-XTAL2-Pad4)") (class "Default")
      (node (ref "U7") (pin "4") (pinfunction "XTAL2_4") (pintype "bidirectional"))
    )
    (net (code "86") (name "unconnected-(U8-CLK-Pad20)") (class "Default")
      (node (ref "U8") (pin "20") (pinfunction "CLK_20") (pintype "bidirectional"))
    )
    (net (code "87") (name "unconnected-(U8-CMD-Pad19)") (class "Default")
      (node (ref "U8") (pin "19") (pinfunction "CMD_19") (pintype "bidirectional"))
    )
    (net (code "88") (name "unconnected-(U8-IO34-Pad6)") (class "Default")
      (node (ref "U8") (pin "6") (pinfunction "IO34_6") (pintype "bidirectional"))
    )
    (net (code "89") (name "unconnected-(U8-SD0-Pad21)") (class "Default")
      (node (ref "U8") (pin "21") (pinfunction "SD0_21") (pintype "bidirectional"))
    )
    (net (code "90") (name "unconnected-(U8-SD1-Pad22)") (class "Default")
      (node (ref "U8") (pin "22") (pinfunction "SD1_22") (pintype "bidirectional"))
    )
    (net (code "91") (name "unconnected-(U8-SD2-Pad17)") (class "Default")
      (node (ref "U8") (pin "17") (pinfunction "SD2_17") (pintype "bidirectional"))
    )
    (net (code "92") (name "unconnected-(U8-SD3-Pad18)") (class "Default")
      (node (ref "U8") (pin "18") (pinfunction "SD3_18") (pintype "bidirectional"))
    )
    (net (code "93") (name "unconnected-(U8-SENSOR_VN-Pad5)") (class "Default")
      (node (ref "U8") (pin "5") (pinfunction "SENSOR_VN_5") (pintype "bidirectional"))
    )
    (net (code "94") (name "unconnected-(U8-SENSOR_VP-Pad4)") (class "Default")
      (node (ref "U8") (pin "4") (pinfunction "SENSOR_VP_4") (pintype "bidirectional"))
    )
  )
)
